# Sheet_2_2021-06-04.net
KiCad netlist of a schematic drawn in Altium Designer
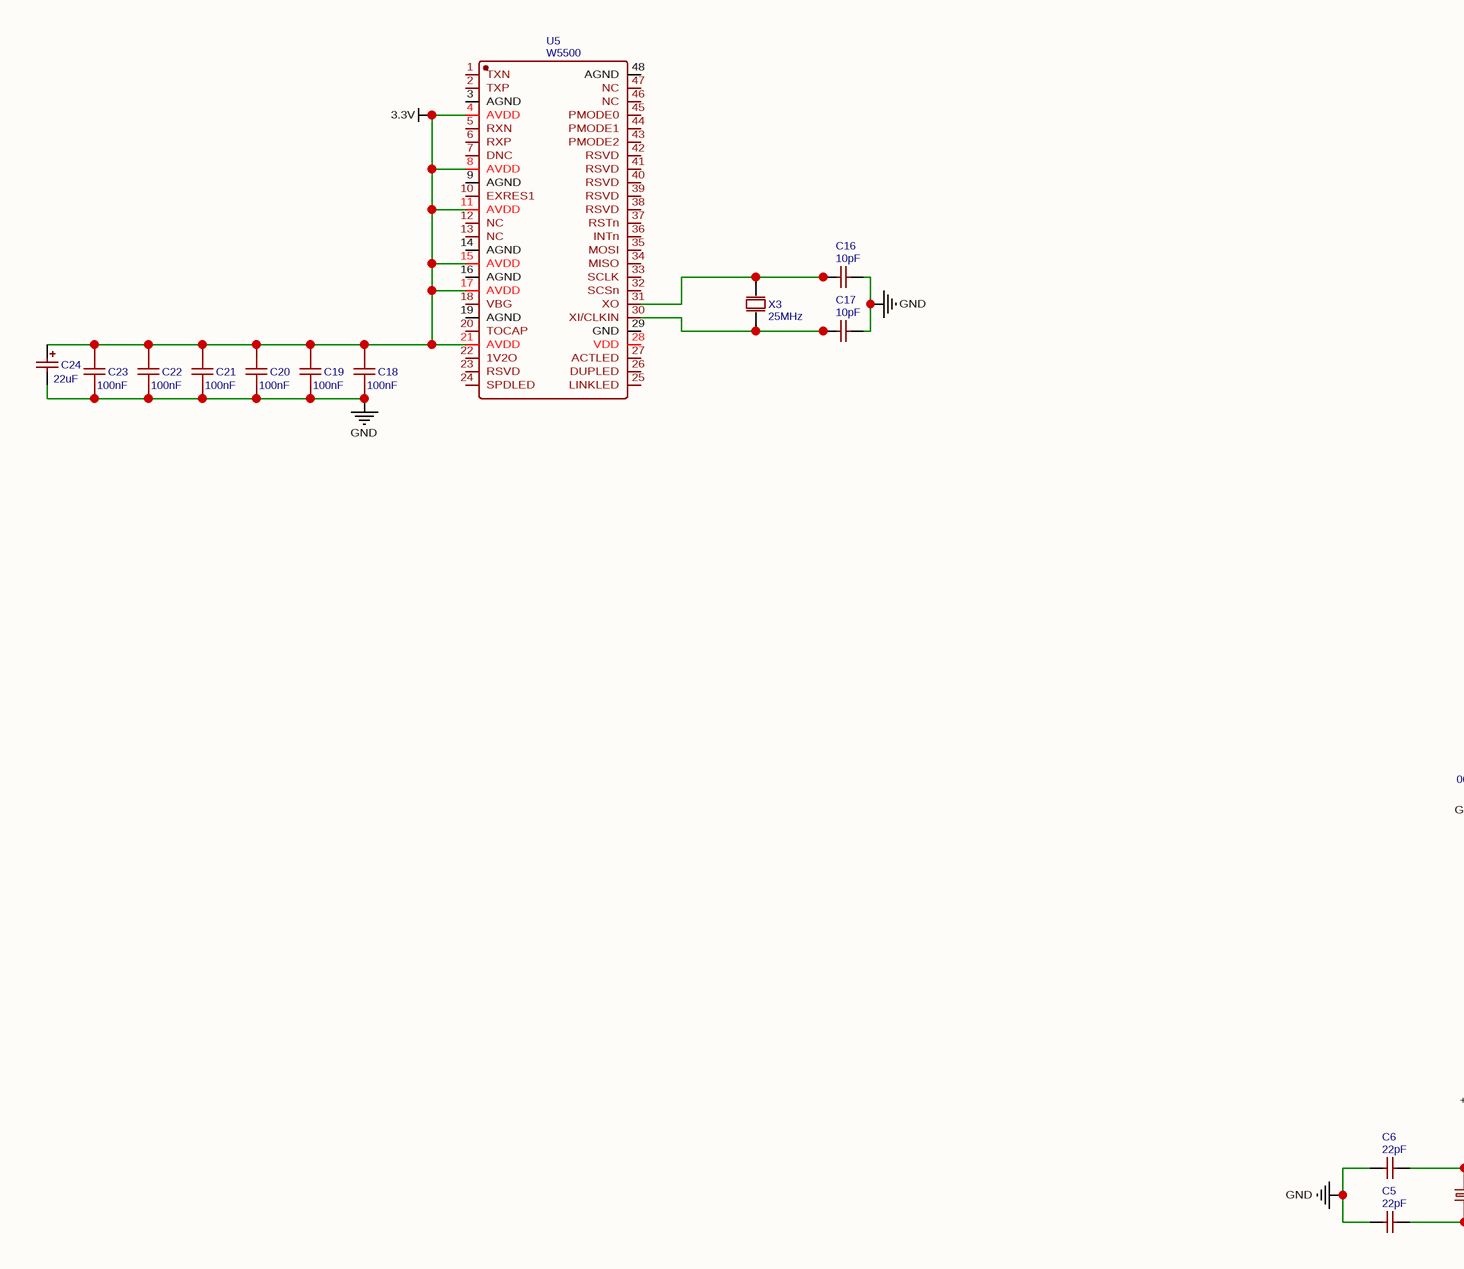
[diagram p0: Sheet_2_2021-06-04.schdoc, left]
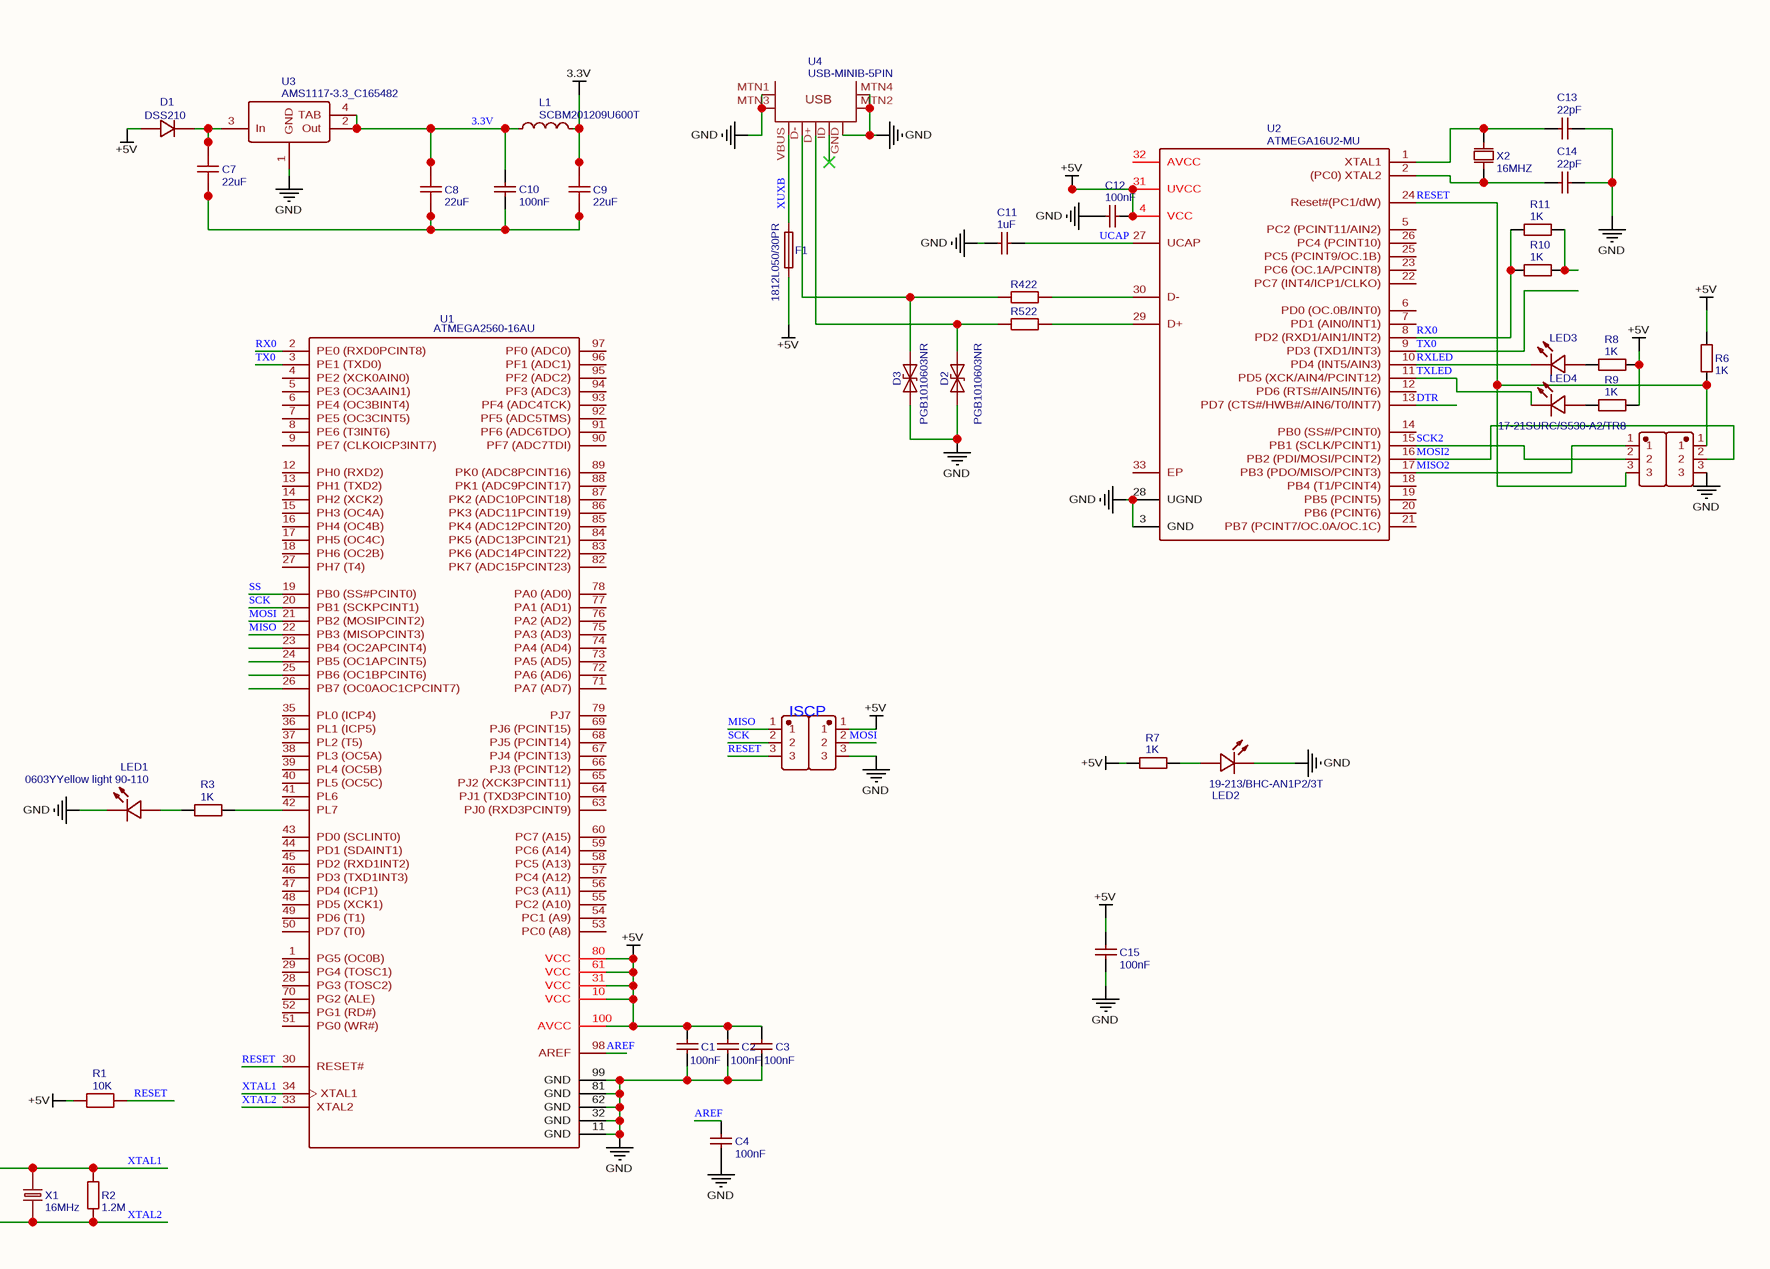
[diagram p1: Sheet_2_2021-06-04.schdoc, right]

(export (version "E")
  (design (tool "Eeschema 10.0.6"))
  (components
    (comp (ref "C1")
      (value "100nF")
      (fields
        (field (name "BOM_MANUFACTURER PART") "CL10B104JB8NNNC")
        (field (name "BOM_SUPPLIER PART") "C24452")
      )
      (libsource (lib "altium-import") (part "root_1_100nF_"))
    )
    (comp (ref "C2")
      (value "100nF")
      (fields
        (field (name "BOM_MANUFACTURER PART") "CL10B104JB8NNNC")
        (field (name "BOM_SUPPLIER PART") "C24452")
      )
      (libsource (lib "altium-import") (part "root_1_100nF_"))
    )
    (comp (ref "C3")
      (value "100nF")
      (fields
        (field (name "BOM_MANUFACTURER PART") "CL10B104JB8NNNC")
        (field (name "BOM_SUPPLIER PART") "C24452")
      )
      (libsource (lib "altium-import") (part "root_1_100nF_"))
    )
    (comp (ref "C4")
      (value "100nF")
      (fields
        (field (name "BOM_MANUFACTURER PART") "CL10B104JB8NNNC")
        (field (name "BOM_SUPPLIER PART") "C24452")
      )
      (libsource (lib "altium-import") (part "root_1_100nF_"))
    )
    (comp (ref "C5")
      (value "22pF")
      (fields
        (field (name "BOM_MANUFACTURER PART") "0201CG220J500NT")
        (field (name "BOM_SUPPLIER PART") "C57783")
      )
      (libsource (lib "altium-import") (part "root_0_22pF_"))
    )
    (comp (ref "C6")
      (value "22pF")
      (fields
        (field (name "BOM_MANUFACTURER PART") "0201CG220J500NT")
        (field (name "BOM_SUPPLIER PART") "C57783")
      )
      (libsource (lib "altium-import") (part "root_0_22pF_"))
    )
    (comp (ref "C7")
      (value "22uF")
      (fields
        (field (name "BOM_MANUFACTURER PART") "1206B226K160NT")
        (field (name "BOM_SUPPLIER PART") "C31847")
      )
      (libsource (lib "altium-import") (part "root_1_22uF_"))
    )
    (comp (ref "C8")
      (value "22uF")
      (fields
        (field (name "BOM_MANUFACTURER PART") "1206B226K160NT")
        (field (name "BOM_SUPPLIER PART") "C31847")
      )
      (libsource (lib "altium-import") (part "root_1_22uF_"))
    )
    (comp (ref "C9")
      (value "22uF")
      (fields
        (field (name "BOM_MANUFACTURER PART") "1206B226K160NT")
        (field (name "BOM_SUPPLIER PART") "C31847")
      )
      (libsource (lib "altium-import") (part "root_1_22uF_"))
    )
    (comp (ref "C10")
      (value "100nF")
      (fields
        (field (name "BOM_MANUFACTURER PART") "0402B104K160NT")
        (field (name "BOM_SUPPLIER PART") "C41851")
      )
      (libsource (lib "altium-import") (part "root_1_100nF_"))
    )
    (comp (ref "C11")
      (value "1uF")
      (fields
        (field (name "BOM_MANUFACTURER PART") "CL10A105KB8NNNC")
        (field (name "BOM_SUPPLIER PART") "C15849")
      )
      (libsource (lib "altium-import") (part "root_0_1uF_"))
    )
    (comp (ref "C12")
      (value "100nF")
      (fields
        (field (name "BOM_MANUFACTURER PART") "CL21F104ZBCNNNC")
        (field (name "BOM_SUPPLIER PART") "C1760")
      )
      (libsource (lib "altium-import") (part "root_0_100nF_"))
    )
    (comp (ref "C13")
      (value "22pF")
      (fields
        (field (name "BOM_MANUFACTURER PART") "0201CG220J500NT")
        (field (name "BOM_SUPPLIER PART") "C57783")
      )
      (libsource (lib "altium-import") (part "root_0_22pF_"))
    )
    (comp (ref "C14")
      (value "22pF")
      (fields
        (field (name "BOM_MANUFACTURER PART") "0201CG220J500NT")
        (field (name "BOM_SUPPLIER PART") "C57783")
      )
      (libsource (lib "altium-import") (part "root_0_22pF_"))
    )
    (comp (ref "C15")
      (value "100nF")
      (fields
        (field (name "BOM_MANUFACTURER PART") "0805B104K500NT")
        (field (name "BOM_SUPPLIER PART") "C38141")
      )
      (libsource (lib "altium-import") (part "root_1_100nF_"))
    )
    (comp (ref "C16")
      (value "10pF")
      (fields
        (field (name "BOM_MANUFACTURER PART") "0603CG100J201NT")
        (field (name "BOM_SUPPLIER PART") "C63673")
      )
      (libsource (lib "altium-import") (part "root_0_10pF_"))
    )
    (comp (ref "C17")
      (value "10pF")
      (fields
        (field (name "BOM_MANUFACTURER PART") "0603CG100J201NT")
        (field (name "BOM_SUPPLIER PART") "C63673")
      )
      (libsource (lib "altium-import") (part "root_0_10pF_"))
    )
    (comp (ref "C18")
      (value "100nF")
      (fields
        (field (name "BOM_MANUFACTURER PART") "GRM319R71H104KA01D")
        (field (name "BOM_SUPPLIER PART") "C86047")
      )
      (libsource (lib "") (part "root_1_100nF__1"))
    )
    (comp (ref "C19")
      (value "100nF")
      (fields
        (field (name "BOM_MANUFACTURER PART") "GRM319R71H104KA01D")
        (field (name "BOM_SUPPLIER PART") "C86047")
      )
      (libsource (lib "") (part "root_1_100nF__1"))
    )
    (comp (ref "C20")
      (value "100nF")
      (fields
        (field (name "BOM_MANUFACTURER PART") "GRM319R71H104KA01D")
        (field (name "BOM_SUPPLIER PART") "C86047")
      )
      (libsource (lib "") (part "root_1_100nF__1"))
    )
    (comp (ref "C21")
      (value "100nF")
      (fields
        (field (name "BOM_MANUFACTURER PART") "GRM319R71H104KA01D")
        (field (name "BOM_SUPPLIER PART") "C86047")
      )
      (libsource (lib "") (part "root_1_100nF__1"))
    )
    (comp (ref "C22")
      (value "100nF")
      (fields
        (field (name "BOM_MANUFACTURER PART") "GRM319R71H104KA01D")
        (field (name "BOM_SUPPLIER PART") "C86047")
      )
      (libsource (lib "") (part "root_1_100nF__1"))
    )
    (comp (ref "C23")
      (value "100nF")
      (fields
        (field (name "BOM_MANUFACTURER PART") "GRM319R71H104KA01D")
        (field (name "BOM_SUPPLIER PART") "C86047")
      )
      (libsource (lib "") (part "root_1_100nF__1"))
    )
    (comp (ref "C24")
      (value "22uF")
      (fields
        (field (name "BOM_MANUFACTURER PART") "CA45A-A-10V-22UF-K")
        (field (name "BOM_SUPPLIER PART") "C141745")
      )
      (libsource (lib "") (part "root_1_22uF__1"))
    )
    (comp (ref "D1")
      (value "DSS210")
      (fields (field (name "BOM_SUPPLIER PART") "C511868") (field (name "CONTRIBUTOR") "LCSC"))
      (libsource (lib "altium-import") (part "root_0_DSS210_"))
    )
    (comp (ref "D2")
      (value "PGB1010603NR")
      (fields (field (name "BOM_SUPPLIER PART") "C10677"))
      (libsource (lib "altium-import") (part "root_1_PGB1010603NR_"))
    )
    (comp (ref "D3")
      (value "PGB1010603NR")
      (fields (field (name "BOM_SUPPLIER PART") "C10677"))
      (libsource (lib "altium-import") (part "root_1_PGB1010603NR_"))
    )
    (comp (ref "F1")
      (value "1812L050/30PR")
      (fields (field (name "BOM_SUPPLIER PART") "C151168") (field (name "CONTRIBUTOR") "LCSC"))
      (libsource (lib "altium-import") (part "root_1_1812L050/30PR_"))
    )
    (comp (ref "H1")
      (value "Z-211-0311-0021-001")
      (fields (field (name "BOM_SUPPLIER PART") "C152153") (field (name "CONTRIBUTOR") "LCSC"))
      (libsource (lib "altium-import") (part "root_0_Z-211-0311-0021-001_"))
    )
    (comp (ref "H2")
      (value "Z-211-0311-0021-001")
      (fields (field (name "BOM_SUPPLIER PART") "C152153") (field (name "CONTRIBUTOR") "LCSC"))
      (libsource (lib "altium-import") (part "root_2_Z-211-0311-0021-001_"))
    )
    (comp (ref "H3")
      (value "Z-211-0311-0021-001")
      (fields (field (name "BOM_SUPPLIER PART") "C152153") (field (name "CONTRIBUTOR") "LCSC"))
      (libsource (lib "altium-import") (part "root_0_Z-211-0311-0021-001_"))
    )
    (comp (ref "H4")
      (value "Z-211-0311-0021-001")
      (fields (field (name "BOM_SUPPLIER PART") "C152153") (field (name "CONTRIBUTOR") "LCSC"))
      (libsource (lib "altium-import") (part "root_2_Z-211-0311-0021-001_"))
    )
    (comp (ref "L1")
      (value "SCBM201209U600T")
      (fields (field (name "BOM_SUPPLIER PART") "C494710") (field (name "CONTRIBUTOR") "LCSC"))
      (libsource (lib "altium-import") (part "root_0_SCBM201209U600T_"))
    )
    (comp (ref "LED1")
      (value "0603YYellow light 90-110")
      (fields
        (field (name "BOM_MANUFACTURER PART") "0603YYellow light 亮度90-110")
        (field (name "BOM_SUPPLIER PART") "C2287")
      )
      (libsource (lib "altium-import") (part "root_0_0603YYellow light 90-110_"))
    )
    (comp (ref "LED2")
      (value "19-213/BHC-AN1P2/3T")
      (fields (field (name "BOM_SUPPLIER PART") "C142304") (field (name "CONTRIBUTOR") "LCSC"))
      (libsource (lib "altium-import") (part "root_2_19-213/BHC-AN1P2/3T_"))
    )
    (comp (ref "LED3")
      (value "17-21SURC/S530-A2/TR8")
      (fields (field (name "BOM_SUPPLIER PART") "C131244") (field (name "CONTRIBUTOR") "LCSC"))
      (libsource (lib "altium-import") (part "root_0_17-21SURC/S530-A2/TR8_"))
    )
    (comp (ref "LED4")
      (value "17-21SURC/S530-A2/TR8")
      (fields (field (name "BOM_SUPPLIER PART") "C131244") (field (name "CONTRIBUTOR") "LCSC"))
      (libsource (lib "altium-import") (part "root_0_17-21SURC/S530-A2/TR8_"))
    )
    (comp (ref "R1")
      (value "10K")
      (fields
        (field (name "BOM_SUPPLIER PART") "C226679")
        (field (name "BOM_MANUFACTURER PART") "AC0402DR-0710KL")
        (field (name "CONTRIBUTOR") "LCSC")
      )
      (libsource (lib "altium-import") (part "root_0_10K_"))
    )
    (comp (ref "R2")
      (value "1.2M")
      (fields
        (field (name "BOM_SUPPLIER PART") "C150391")
        (field (name "BOM_MANUFACTURER PART") "HCR32-125FV")
        (field (name "CONTRIBUTOR") "LCSC")
      )
      (libsource (lib "altium-import") (part "root_1_1.2M_"))
    )
    (comp (ref "R3")
      (value "1K")
      (fields
        (field (name "BOM_MANUFACTURER PART") "1206W4F1001T5E")
        (field (name "BOM_SUPPLIER PART") "C4410")
      )
      (libsource (lib "altium-import") (part "root_0_1K_"))
    )
    (comp (ref "R4")
      (value "22")
      (fields
        (field (name "BOM_SUPPLIER PART") "C144722")
        (field (name "BOM_MANUFACTURER PART") "AC0402JR-0722RL")
        (field (name "CONTRIBUTOR") "LCSC")
      )
      (libsource (lib "altium-import") (part "root_0_22_"))
    )
    (comp (ref "R5")
      (value "22")
      (fields
        (field (name "BOM_SUPPLIER PART") "C144722")
        (field (name "BOM_MANUFACTURER PART") "AC0402JR-0722RL")
        (field (name "CONTRIBUTOR") "LCSC")
      )
      (libsource (lib "altium-import") (part "root_0_22_"))
    )
    (comp (ref "R6")
      (value "1K")
      (fields
        (field (name "BOM_MANUFACTURER PART") "1206W4F1001T5E")
        (field (name "BOM_SUPPLIER PART") "C4410")
      )
      (libsource (lib "altium-import") (part "root_1_1K_"))
    )
    (comp (ref "R7")
      (value "1K")
      (fields
        (field (name "BOM_MANUFACTURER PART") "1206W4J0102T5E")
        (field (name "BOM_SUPPLIER PART") "C1469")
      )
      (libsource (lib "altium-import") (part "root_0_1K_"))
    )
    (comp (ref "R8")
      (value "1K")
      (fields
        (field (name "BOM_MANUFACTURER PART") "1206W4J0102T5E")
        (field (name "BOM_SUPPLIER PART") "C1469")
      )
      (libsource (lib "altium-import") (part "root_0_1K_"))
    )
    (comp (ref "R9")
      (value "1K")
      (fields
        (field (name "BOM_MANUFACTURER PART") "1206W4J0102T5E")
        (field (name "BOM_SUPPLIER PART") "C1469")
      )
      (libsource (lib "altium-import") (part "root_0_1K_"))
    )
    (comp (ref "R10")
      (value "1K")
      (fields
        (field (name "BOM_MANUFACTURER PART") "RS-05K102JT")
        (field (name "BOM_SUPPLIER PART") "C115302")
      )
      (libsource (lib "altium-import") (part "root_0_1K_"))
    )
    (comp (ref "R11")
      (value "1K")
      (fields
        (field (name "BOM_MANUFACTURER PART") "RS-05K102JT")
        (field (name "BOM_SUPPLIER PART") "C115302")
      )
      (libsource (lib "altium-import") (part "root_0_1K_"))
    )
    (comp (ref "U1")
      (value "ATMEGA2560-16AU")
      (fields (field (name "BOM_SUPPLIER PART") "C22460"))
      (libsource (lib "altium-import") (part "root_0_ATMEGA2560-16AU_"))
    )
    (comp (ref "U2")
      (value "ATMEGA16U2-MU")
      (fields (field (name "BOM_SUPPLIER PART") "C17317"))
      (libsource (lib "altium-import") (part "root_0_ATMEGA16U2-MU_"))
    )
    (comp (ref "U3")
      (value "AMS1117-3.3_C165482")
      (fields
        (field (name "BOM_SUPPLIER PART") "C165482")
        (field (name "BOM_MANUFACTURER PART") "AMS1117-3.3")
        (field (name "CONTRIBUTOR") "LCSC")
      )
      (libsource (lib "altium-import") (part "root_0_AMS1117-3.3_C165482_"))
    )
    (comp (ref "U4")
      (value "USB-MINIB-5PIN")
      (description "Mini-USB B connector with 5th pin broken out.")
      (fields (field (name "CONTRIBUTOR") "SparkFun"))
      (libsource (lib "altium-import") (part "root_1_USB-MINIB-5PIN_"))
    )
    (comp (ref "U5")
      (value "W5500")
      (fields (field (name "BOM_SUPPLIER PART") "C32843"))
      (libsource (lib "altium-import") (part "root_0_W5500_"))
    )
    (comp (ref "X1")
      (value "16MHz")
      (fields
        (field (name "BOM_MANUFACTURER PART") "HC-49SM16MHz20pF30ppm")
        (field (name "BOM_SUPPLIER PART") "C111377")
      )
      (libsource (lib "altium-import") (part "root_1_16MHz_"))
    )
    (comp (ref "X2")
      (value "16MHZ")
      (fields
        (field (name "BOM_SUPPLIER PART") "C390745")
        (field (name "BOM_MANUFACTURER PART") "49SAC16000202060")
        (field (name "CONTRIBUTOR") "LCSC")
      )
      (libsource (lib "altium-import") (part "root_1_16MHZ_"))
    )
    (comp (ref "X3")
      (value "25MHz")
      (fields
        (field (name "BOM_MANUFACTURER PART") "X49SM25MSD2SC")
        (field (name "BOM_SUPPLIER PART") "C14872")
      )
      (libsource (lib "altium-import") (part "root_1_25MHz_"))
    )
  )
  (nets
    (net (code "1") (name "+5V") (class "Default")
      (node (ref "C1") (pin "2") (pinfunction "2_2") (pintype "passive"))
      (node (ref "C12") (pin "2") (pinfunction "2_2") (pintype "passive"))
      (node (ref "C15") (pin "2") (pinfunction "2_2") (pintype "passive"))
      (node (ref "C2") (pin "2") (pinfunction "2_2") (pintype "passive"))
      (node (ref "C3") (pin "2") (pinfunction "2_2") (pintype "passive"))
      (node (ref "D1") (pin "1") (pinfunction "A_1") (pintype "passive"))
      (node (ref "F1") (pin "1") (pinfunction "1_1") (pintype "passive"))
      (node (ref "H2") (pin "1") (pinfunction "1_1") (pintype "passive"))
      (node (ref "R1") (pin "1") (pinfunction "1_1") (pintype "passive"))
      (node (ref "R6") (pin "2") (pinfunction "2_2") (pintype "passive"))
      (node (ref "R7") (pin "1") (pinfunction "1_1") (pintype "passive"))
      (node (ref "R8") (pin "2") (pinfunction "2_2") (pintype "passive"))
      (node (ref "R9") (pin "2") (pinfunction "2_2") (pintype "passive"))
      (node (ref "U1") (pin "10") (pinfunction "VCC_10") (pintype "passive"))
      (node (ref "U1") (pin "100") (pinfunction "AVCC_100") (pintype "passive"))
      (node (ref "U1") (pin "31") (pinfunction "VCC_31") (pintype "passive"))
      (node (ref "U1") (pin "61") (pinfunction "VCC_61") (pintype "passive"))
      (node (ref "U1") (pin "80") (pinfunction "VCC_80") (pintype "passive"))
      (node (ref "U2") (pin "31") (pinfunction "UVCC_31") (pintype "passive"))
      (node (ref "U2") (pin "4") (pinfunction "VCC_4") (pintype "passive"))
    )
    (net (code "2") (name "/AREF") (class "Default")
      (node (ref "C4") (pin "2") (pinfunction "2_2") (pintype "passive"))
      (node (ref "U1") (pin "98") (pinfunction "AREF_98") (pintype "passive"))
    )
    (net (code "3") (name "/DTR") (class "Default")
      (node (ref "U2") (pin "13") (pinfunction "PD7_(CTS#/HWB#/AIN6/T0/INT7)_13") (pintype "passive"))
    )
    (net (code "4") (name "/MISO") (class "Default")
      (node (ref "H1") (pin "1") (pinfunction "1_1") (pintype "passive"))
      (node (ref "U1") (pin "22") (pinfunction "PB3_(MISOPCINT3)_22") (pintype "passive"))
    )
    (net (code "5") (name "/MISO2") (class "Default")
      (node (ref "H3") (pin "1") (pinfunction "1_1") (pintype "passive"))
      (node (ref "U2") (pin "17") (pinfunction "PB3_(PDO/MISO/PCINT3)_17") (pintype "passive"))
    )
    (net (code "6") (name "/MOSI") (class "Default")
      (node (ref "H2") (pin "2") (pinfunction "2_2") (pintype "passive"))
      (node (ref "U1") (pin "21") (pinfunction "PB2_(MOSIPCINT2)_21") (pintype "passive"))
    )
    (net (code "7") (name "/MOSI2") (class "Default")
      (node (ref "H4") (pin "2") (pinfunction "2_2") (pintype "passive"))
      (node (ref "U2") (pin "16") (pinfunction "PB2_(PDI/MOSI/PCINT2)_16") (pintype "passive"))
    )
    (net (code "8") (name "/RESET") (class "Default")
      (node (ref "H1") (pin "3") (pinfunction "3_3") (pintype "passive"))
      (node (ref "H3") (pin "3") (pinfunction "3_3") (pintype "passive"))
      (node (ref "H4") (pin "1") (pinfunction "1_1") (pintype "passive"))
      (node (ref "R1") (pin "2") (pinfunction "2_2") (pintype "passive"))
      (node (ref "R6") (pin "1") (pinfunction "1_1") (pintype "passive"))
      (node (ref "U1") (pin "30") (pinfunction "RESET#_30") (pintype "passive"))
      (node (ref "U2") (pin "24") (pinfunction "Reset#(PC1/dW)_24") (pintype "passive"))
    )
    (net (code "9") (name "/RX0") (class "Default")
      (node (ref "R10") (pin "1") (pinfunction "1_1") (pintype "passive"))
      (node (ref "R11") (pin "1") (pinfunction "1_1") (pintype "passive"))
      (node (ref "U1") (pin "2") (pinfunction "PE0_(RXD0PCINT8)_2") (pintype "passive"))
      (node (ref "U2") (pin "8") (pinfunction "PD2_(RXD1/AIN1/INT2)_8") (pintype "passive"))
    )
    (net (code "10") (name "/RXLED") (class "Default")
      (node (ref "LED3") (pin "1") (pinfunction "K_1") (pintype "passive"))
      (node (ref "U2") (pin "10") (pinfunction "PD4_(INT5/AIN3)_10") (pintype "passive"))
    )
    (net (code "11") (name "/SCK") (class "Default")
      (node (ref "H1") (pin "2") (pinfunction "2_2") (pintype "passive"))
      (node (ref "U1") (pin "20") (pinfunction "PB1_(SCKPCINT1)_20") (pintype "passive"))
    )
    (net (code "12") (name "/SCK2") (class "Default")
      (node (ref "H3") (pin "2") (pinfunction "2_2") (pintype "passive"))
      (node (ref "U2") (pin "15") (pinfunction "PB1_(SCLK/PCINT1)_15") (pintype "passive"))
    )
    (net (code "13") (name "/SS") (class "Default")
      (node (ref "U1") (pin "19") (pinfunction "PB0_(SS#PCINT0)_19") (pintype "passive"))
    )
    (net (code "14") (name "/TX0") (class "Default")
      (node (ref "U1") (pin "3") (pinfunction "PE1_(TXD0)_3") (pintype "passive"))
      (node (ref "U2") (pin "9") (pinfunction "PD3_(TXD1/INT3)_9") (pintype "passive"))
    )
    (net (code "15") (name "/TXLED") (class "Default")
      (node (ref "LED4") (pin "1") (pinfunction "K_1") (pintype "passive"))
      (node (ref "U2") (pin "11") (pinfunction "PD5_(XCK/AIN4/PCINT12)_11") (pintype "passive"))
    )
    (net (code "16") (name "/UCAP") (class "Default")
      (node (ref "C11") (pin "2") (pinfunction "2_2") (pintype "passive"))
      (node (ref "U2") (pin "27") (pinfunction "UCAP_27") (pintype "passive"))
    )
    (net (code "17") (name "/XTAL1") (class "Default")
      (node (ref "C6") (pin "2") (pinfunction "2_2") (pintype "passive"))
      (node (ref "R2") (pin "2") (pinfunction "2_2") (pintype "passive"))
      (node (ref "U1") (pin "34") (pinfunction "XTAL1_34") (pintype "passive"))
      (node (ref "X1") (pin "2") (pinfunction "2_2") (pintype "passive"))
    )
    (net (code "18") (name "/XTAL2") (class "Default")
      (node (ref "C5") (pin "2") (pinfunction "2_2") (pintype "passive"))
      (node (ref "R2") (pin "1") (pinfunction "1_1") (pintype "passive"))
      (node (ref "U1") (pin "33") (pinfunction "XTAL2_33") (pintype "passive"))
      (node (ref "X1") (pin "1") (pinfunction "1_1") (pintype "passive"))
    )
    (net (code "19") (name "/XUXB") (class "Default")
      (node (ref "F1") (pin "2") (pinfunction "2_2") (pintype "passive"))
      (node (ref "U4") (pin "VBUS") (pinfunction "VBUS_VBUS") (pintype "passive"))
    )
    (net (code "20") (name "3.3V") (class "Default")
      (node (ref "C10") (pin "2") (pinfunction "2_2") (pintype "passive"))
      (node (ref "C18") (pin "2") (pinfunction "2_2") (pintype "passive"))
      (node (ref "C19") (pin "2") (pinfunction "2_2") (pintype "passive"))
      (node (ref "C20") (pin "2") (pinfunction "2_2") (pintype "passive"))
      (node (ref "C21") (pin "2") (pinfunction "2_2") (pintype "passive"))
      (node (ref "C22") (pin "2") (pinfunction "2_2") (pintype "passive"))
      (node (ref "C23") (pin "2") (pinfunction "2_2") (pintype "passive"))
      (node (ref "C24") (pin "1") (pinfunction "1_1") (pintype "passive"))
      (node (ref "C8") (pin "2") (pinfunction "2_2") (pintype "passive"))
      (node (ref "C9") (pin "2") (pinfunction "2_2") (pintype "passive"))
      (node (ref "L1") (pin "1") (pinfunction "1_1") (pintype "passive"))
      (node (ref "L1") (pin "2") (pinfunction "2_2") (pintype "passive"))
      (node (ref "U3") (pin "2") (pinfunction "Out_2") (pintype "passive"))
      (node (ref "U3") (pin "4") (pinfunction "TAB_4") (pintype "passive"))
      (node (ref "U5") (pin "11") (pinfunction "AVDD_11") (pintype "passive"))
      (node (ref "U5") (pin "15") (pinfunction "AVDD_15") (pintype "passive"))
      (node (ref "U5") (pin "17") (pinfunction "AVDD_17") (pintype "passive"))
      (node (ref "U5") (pin "21") (pinfunction "AVDD_21") (pintype "passive"))
      (node (ref "U5") (pin "4") (pinfunction "AVDD_4") (pintype "passive"))
      (node (ref "U5") (pin "8") (pinfunction "AVDD_8") (pintype "passive"))
    )
    (net (code "21") (name "GND") (class "Default")
      (node (ref "C1") (pin "1") (pinfunction "1_1") (pintype "passive"))
      (node (ref "C11") (pin "1") (pinfunction "1_1") (pintype "passive"))
      (node (ref "C12") (pin "1") (pinfunction "1_1") (pintype "passive"))
      (node (ref "C13") (pin "2") (pinfunction "2_2") (pintype "passive"))
      (node (ref "C14") (pin "2") (pinfunction "2_2") (pintype "passive"))
      (node (ref "C15") (pin "1") (pinfunction "1_1") (pintype "passive"))
      (node (ref "C16") (pin "2") (pinfunction "2_2") (pintype "passive"))
      (node (ref "C17") (pin "2") (pinfunction "2_2") (pintype "passive"))
      (node (ref "C18") (pin "1") (pinfunction "1_1") (pintype "passive"))
      (node (ref "C19") (pin "1") (pinfunction "1_1") (pintype "passive"))
      (node (ref "C2") (pin "1") (pinfunction "1_1") (pintype "passive"))
      (node (ref "C20") (pin "1") (pinfunction "1_1") (pintype "passive"))
      (node (ref "C21") (pin "1") (pinfunction "1_1") (pintype "passive"))
      (node (ref "C22") (pin "1") (pinfunction "1_1") (pintype "passive"))
      (node (ref "C23") (pin "1") (pinfunction "1_1") (pintype "passive"))
      (node (ref "C24") (pin "2") (pinfunction "2_2") (pintype "passive"))
      (node (ref "C3") (pin "1") (pinfunction "1_1") (pintype "passive"))
      (node (ref "C4") (pin "1") (pinfunction "1_1") (pintype "passive"))
      (node (ref "C5") (pin "1") (pinfunction "1_1") (pintype "passive"))
      (node (ref "C6") (pin "1") (pinfunction "1_1") (pintype "passive"))
      (node (ref "D2") (pin "1") (pinfunction "1_1") (pintype "passive"))
      (node (ref "D3") (pin "1") (pinfunction "1_1") (pintype "passive"))
      (node (ref "H2") (pin "3") (pinfunction "3_3") (pintype "passive"))
      (node (ref "H4") (pin "3") (pinfunction "3_3") (pintype "passive"))
      (node (ref "LED1") (pin "2") (pinfunction "K_2") (pintype "passive"))
      (node (ref "LED2") (pin "1") (pinfunction "K_1") (pintype "passive"))
      (node (ref "U1") (pin "11") (pinfunction "GND_11") (pintype "passive"))
      (node (ref "U1") (pin "32") (pinfunction "GND_32") (pintype "passive"))
      (node (ref "U1") (pin "62") (pinfunction "GND_62") (pintype "passive"))
      (node (ref "U1") (pin "81") (pinfunction "GND_81") (pintype "passive"))
      (node (ref "U1") (pin "99") (pinfunction "GND_99") (pintype "passive"))
      (node (ref "U2") (pin "28") (pinfunction "UGND_28") (pintype "passive"))
      (node (ref "U2") (pin "3") (pinfunction "GND_3") (pintype "passive"))
      (node (ref "U3") (pin "1") (pinfunction "GND_1") (pintype "passive"))
      (node (ref "U4") (pin "GND") (pinfunction "GND_GND") (pintype "passive"))
      (node (ref "U4") (pin "MTN1") (pinfunction "MTN2_MTN1") (pintype "passive"))
      (node (ref "U4") (pin "MTN2") (pinfunction "MTN3_MTN2") (pintype "passive"))
      (node (ref "U4") (pin "MTN3") (pinfunction "MTN1_MTN3") (pintype "passive"))
      (node (ref "U4") (pin "MTN4") (pinfunction "MTN4_MTN4") (pintype "passive"))
    )
    (net (code "22") (name "Net-(C10-Pad1)") (class "Default")
      (node (ref "C10") (pin "1") (pinfunction "1_1") (pintype "passive"))
      (node (ref "C7") (pin "1") (pinfunction "1_1") (pintype "passive"))
      (node (ref "C8") (pin "1") (pinfunction "1_1") (pintype "passive"))
      (node (ref "C9") (pin "1") (pinfunction "1_1") (pintype "passive"))
    )
    (net (code "23") (name "Net-(D1-K)") (class "Default")
      (node (ref "C7") (pin "2") (pinfunction "2_2") (pintype "passive"))
      (node (ref "D1") (pin "2") (pinfunction "K_2") (pintype "passive"))
      (node (ref "U3") (pin "3") (pinfunction "In_3") (pintype "passive"))
    )
    (net (code "24") (name "Net-(D2-Pad2)") (class "Default")
      (node (ref "D2") (pin "2") (pinfunction "2_2") (pintype "passive"))
      (node (ref "R5") (pin "1") (pinfunction "1_1") (pintype "passive"))
      (node (ref "U4") (pin "D+") (pinfunction "D+_D+") (pintype "passive"))
    )
    (net (code "25") (name "Net-(D3-Pad2)") (class "Default")
      (node (ref "D3") (pin "2") (pinfunction "2_2") (pintype "passive"))
      (node (ref "R4") (pin "1") (pinfunction "1_1") (pintype "passive"))
      (node (ref "U4") (pin "D-") (pinfunction "D-_D-") (pintype "passive"))
    )
    (net (code "26") (name "Net-(LED1-A)") (class "Default")
      (node (ref "LED1") (pin "1") (pinfunction "A_1") (pintype "passive"))
      (node (ref "R3") (pin "1") (pinfunction "1_1") (pintype "passive"))
    )
    (net (code "27") (name "Net-(LED2-A)") (class "Default")
      (node (ref "LED2") (pin "2") (pinfunction "A_2") (pintype "passive"))
      (node (ref "R7") (pin "2") (pinfunction "2_2") (pintype "passive"))
    )
    (net (code "28") (name "Net-(LED3-A)") (class "Default")
      (node (ref "LED3") (pin "2") (pinfunction "A_2") (pintype "passive"))
      (node (ref "R8") (pin "1") (pinfunction "1_1") (pintype "passive"))
    )
    (net (code "29") (name "Net-(LED4-A)") (class "Default")
      (node (ref "LED4") (pin "2") (pinfunction "A_2") (pintype "passive"))
      (node (ref "R9") (pin "1") (pinfunction "1_1") (pintype "passive"))
    )
    (net (code "30") (name "Net-(R10-Pad2)") (class "Default")
      (node (ref "R10") (pin "2") (pinfunction "2_2") (pintype "passive"))
      (node (ref "R11") (pin "2") (pinfunction "2_2") (pintype "passive"))
    )
    (net (code "31") (name "Net-(U1-PL7)") (class "Default")
      (node (ref "R3") (pin "2") (pinfunction "2_2") (pintype "passive"))
      (node (ref "U1") (pin "42") (pinfunction "PL7_42") (pintype "passive"))
    )
    (net (code "32") (name "Net-(U2-(PC0)_XTAL2)") (class "Default")
      (node (ref "C14") (pin "1") (pinfunction "1_1") (pintype "passive"))
      (node (ref "U2") (pin "2") (pinfunction "(PC0)_XTAL2_2") (pintype "passive"))
      (node (ref "X2") (pin "1") (pinfunction "OSC1_1") (pintype "passive"))
    )
    (net (code "33") (name "Net-(U2-D+)") (class "Default")
      (node (ref "R5") (pin "2") (pinfunction "2_2") (pintype "passive"))
      (node (ref "U2") (pin "29") (pinfunction "D+_29") (pintype "passive"))
    )
    (net (code "34") (name "Net-(U2-D-)") (class "Default")
      (node (ref "R4") (pin "2") (pinfunction "2_2") (pintype "passive"))
      (node (ref "U2") (pin "30") (pinfunction "D-_30") (pintype "passive"))
    )
    (net (code "35") (name "Net-(U2-XTAL1)") (class "Default")
      (node (ref "C13") (pin "1") (pinfunction "1_1") (pintype "passive"))
      (node (ref "U2") (pin "1") (pinfunction "XTAL1_1") (pintype "passive"))
      (node (ref "X2") (pin "2") (pinfunction "OSC2_2") (pintype "passive"))
    )
    (net (code "36") (name "Net-(U5-XI{slash}CLKIN)") (class "Default")
      (node (ref "C17") (pin "1") (pinfunction "1_1") (pintype "passive"))
      (node (ref "U5") (pin "30") (pinfunction "XI/CLKIN_30") (pintype "passive"))
      (node (ref "X3") (pin "1") (pinfunction "OSC1_1") (pintype "passive"))
    )
    (net (code "37") (name "Net-(U5-XO)") (class "Default")
      (node (ref "C16") (pin "1") (pinfunction "1_1") (pintype "passive"))
      (node (ref "U5") (pin "31") (pinfunction "XO_31") (pintype "passive"))
      (node (ref "X3") (pin "2") (pinfunction "OSC2_2") (pintype "passive"))
    )
    (net (code "38") (name "unconnected-(U1-PA0_(AD0)-Pad78)") (class "Default")
      (node (ref "U1") (pin "78") (pinfunction "PA0_(AD0)_78") (pintype "passive"))
    )
    (net (code "39") (name "unconnected-(U1-PA1_(AD1)-Pad77)") (class "Default")
      (node (ref "U1") (pin "77") (pinfunction "PA1_(AD1)_77") (pintype "passive"))
    )
    (net (code "40") (name "unconnected-(U1-PA2_(AD2)-Pad76)") (class "Default")
      (node (ref "U1") (pin "76") (pinfunction "PA2_(AD2)_76") (pintype "passive"))
    )
    (net (code "41") (name "unconnected-(U1-PA3_(AD3)-Pad75)") (class "Default")
      (node (ref "U1") (pin "75") (pinfunction "PA3_(AD3)_75") (pintype "passive"))
    )
    (net (code "42") (name "unconnected-(U1-PA4_(AD4)-Pad74)") (class "Default")
      (node (ref "U1") (pin "74") (pinfunction "PA4_(AD4)_74") (pintype "passive"))
    )
    (net (code "43") (name "unconnected-(U1-PA5_(AD5)-Pad73)") (class "Default")
      (node (ref "U1") (pin "73") (pinfunction "PA5_(AD5)_73") (pintype "passive"))
    )
    (net (code "44") (name "unconnected-(U1-PA6_(AD6)-Pad72)") (class "Default")
      (node (ref "U1") (pin "72") (pinfunction "PA6_(AD6)_72") (pintype "passive"))
    )
    (net (code "45") (name "unconnected-(U1-PA7_(AD7)-Pad71)") (class "Default")
      (node (ref "U1") (pin "71") (pinfunction "PA7_(AD7)_71") (pintype "passive"))
    )
    (net (code "46") (name "unconnected-(U1-PB4_(OC2APCINT4)-Pad23)") (class "Default")
      (node (ref "U1") (pin "23") (pinfunction "PB4_(OC2APCINT4)_23") (pintype "passive"))
    )
    (net (code "47") (name "unconnected-(U1-PB5_(OC1APCINT5)-Pad24)") (class "Default")
      (node (ref "U1") (pin "24") (pinfunction "PB5_(OC1APCINT5)_24") (pintype "passive"))
    )
    (net (code "48") (name "unconnected-(U1-PB6_(OC1BPCINT6)-Pad25)") (class "Default")
      (node (ref "U1") (pin "25") (pinfunction "PB6_(OC1BPCINT6)_25") (pintype "passive"))
    )
    (net (code "49") (name "unconnected-(U1-PB7_(OC0AOC1CPCINT7)-Pad26)") (class "Default")
      (node (ref "U1") (pin "26") (pinfunction "PB7_(OC0AOC1CPCINT7)_26") (pintype "passive"))
    )
    (net (code "50") (name "unconnected-(U1-PC0_(A8)-Pad53)") (class "Default")
      (node (ref "U1") (pin "53") (pinfunction "PC0_(A8)_53") (pintype "passive"))
    )
    (net (code "51") (name "unconnected-(U1-PC1_(A9)-Pad54)") (class "Default")
      (node (ref "U1") (pin "54") (pinfunction "PC1_(A9)_54") (pintype "passive"))
    )
    (net (code "52") (name "unconnected-(U1-PC2_(A10)-Pad55)") (class "Default")
      (node (ref "U1") (pin "55") (pinfunction "PC2_(A10)_55") (pintype "passive"))
    )
    (net (code "53") (name "unconnected-(U1-PC3_(A11)-Pad56)") (class "Default")
      (node (ref "U1") (pin "56") (pinfunction "PC3_(A11)_56") (pintype "passive"))
    )
    (net (code "54") (name "unconnected-(U1-PC4_(A12)-Pad57)") (class "Default")
      (node (ref "U1") (pin "57") (pinfunction "PC4_(A12)_57") (pintype "passive"))
    )
    (net (code "55") (name "unconnected-(U1-PC5_(A13)-Pad58)") (class "Default")
      (node (ref "U1") (pin "58") (pinfunction "PC5_(A13)_58") (pintype "passive"))
    )
    (net (code "56") (name "unconnected-(U1-PC6_(A14)-Pad59)") (class "Default")
      (node (ref "U1") (pin "59") (pinfunction "PC6_(A14)_59") (pintype "passive"))
    )
    (net (code "57") (name "unconnected-(U1-PC7_(A15)-Pad60)") (class "Default")
      (node (ref "U1") (pin "60") (pinfunction "PC7_(A15)_60") (pintype "passive"))
    )
    (net (code "58") (name "unconnected-(U1-PD0_(SCLINT0)-Pad43)") (class "Default")
      (node (ref "U1") (pin "43") (pinfunction "PD0_(SCLINT0)_43") (pintype "passive"))
    )
    (net (code "59") (name "unconnected-(U1-PD1_(SDAINT1)-Pad44)") (class "Default")
      (node (ref "U1") (pin "44") (pinfunction "PD1_(SDAINT1)_44") (pintype "passive"))
    )
    (net (code "60") (name "unconnected-(U1-PD2_(RXD1INT2)-Pad45)") (class "Default")
      (node (ref "U1") (pin "45") (pinfunction "PD2_(RXD1INT2)_45") (pintype "passive"))
    )
    (net (code "61") (name "unconnected-(U1-PD3_(TXD1INT3)-Pad46)") (class "Default")
      (node (ref "U1") (pin "46") (pinfunction "PD3_(TXD1INT3)_46") (pintype "passive"))
    )
    (net (code "62") (name "unconnected-(U1-PD4_(ICP1)-Pad47)") (class "Default")
      (node (ref "U1") (pin "47") (pinfunction "PD4_(ICP1)_47") (pintype "passive"))
    )
    (net (code "63") (name "unconnected-(U1-PD5_(XCK1)-Pad48)") (class "Default")
      (node (ref "U1") (pin "48") (pinfunction "PD5_(XCK1)_48") (pintype "passive"))
    )
    (net (code "64") (name "unconnected-(U1-PD6_(T1)-Pad49)") (class "Default")
      (node (ref "U1") (pin "49") (pinfunction "PD6_(T1)_49") (pintype "passive"))
    )
    (net (code "65") (name "unconnected-(U1-PD7_(T0)-Pad50)") (class "Default")
      (node (ref "U1") (pin "50") (pinfunction "PD7_(T0)_50") (pintype "passive"))
    )
    (net (code "66") (name "unconnected-(U1-PE2_(XCK0AIN0)-Pad4)") (class "Default")
      (node (ref "U1") (pin "4") (pinfunction "PE2_(XCK0AIN0)_4") (pintype "passive"))
    )
    (net (code "67") (name "unconnected-(U1-PE3_(OC3AAIN1)-Pad5)") (class "Default")
      (node (ref "U1") (pin "5") (pinfunction "PE3_(OC3AAIN1)_5") (pintype "passive"))
    )
    (net (code "68") (name "unconnected-(U1-PE4_(OC3BINT4)-Pad6)") (class "Default")
      (node (ref "U1") (pin "6") (pinfunction "PE4_(OC3BINT4)_6") (pintype "passive"))
    )
    (net (code "69") (name "unconnected-(U1-PE5_(OC3CINT5)-Pad7)") (class "Default")
      (node (ref "U1") (pin "7") (pinfunction "PE5_(OC3CINT5)_7") (pintype "passive"))
    )
    (net (code "70") (name "unconnected-(U1-PE6_(T3INT6)-Pad8)") (class "Default")
      (node (ref "U1") (pin "8") (pinfunction "PE6_(T3INT6)_8") (pintype "passive"))
    )
    (net (code "71") (name "unconnected-(U1-PE7_(CLKOICP3INT7)-Pad9)") (class "Default")
      (node (ref "U1") (pin "9") (pinfunction "PE7_(CLKOICP3INT7)_9") (pintype "passive"))
    )
    (net (code "72") (name "unconnected-(U1-PF0_(ADC0)-Pad97)") (class "Default")
      (node (ref "U1") (pin "97") (pinfunction "PF0_(ADC0)_97") (pintype "passive"))
    )
    (net (code "73") (name "unconnected-(U1-PF1_(ADC1)-Pad96)") (class "Default")
      (node (ref "U1") (pin "96") (pinfunction "PF1_(ADC1)_96") (pintype "passive"))
    )
    (net (code "74") (name "unconnected-(U1-PF2_(ADC2)-Pad95)") (class "Default")
      (node (ref "U1") (pin "95") (pinfunction "PF2_(ADC2)_95") (pintype "passive"))
    )
    (net (code "75") (name "unconnected-(U1-PF3_(ADC3)-Pad94)") (class "Default")
      (node (ref "U1") (pin "94") (pinfunction "PF3_(ADC3)_94") (pintype "passive"))
    )
    (net (code "76") (name "unconnected-(U1-PF4_(ADC4TCK)-Pad93)") (class "Default")
      (node (ref "U1") (pin "93") (pinfunction "PF4_(ADC4TCK)_93") (pintype "passive"))
    )
    (net (code "77") (name "unconnected-(U1-PF5_(ADC5TMS)-Pad92)") (class "Default")
      (node (ref "U1") (pin "92") (pinfunction "PF5_(ADC5TMS)_92") (pintype "passive"))
    )
    (net (code "78") (name "unconnected-(U1-PF6_(ADC6TDO)-Pad91)") (class "Default")
      (node (ref "U1") (pin "91") (pinfunction "PF6_(ADC6TDO)_91") (pintype "passive"))
    )
    (net (code "79") (name "unconnected-(U1-PF7_(ADC7TDI)-Pad90)") (class "Default")
      (node (ref "U1") (pin "90") (pinfunction "PF7_(ADC7TDI)_90") (pintype "passive"))
    )
    (net (code "80") (name "unconnected-(U1-PG0_(WR#)-Pad51)") (class "Default")
      (node (ref "U1") (pin "51") (pinfunction "PG0_(WR#)_51") (pintype "passive"))
    )
    (net (code "81") (name "unconnected-(U1-PG1_(RD#)-Pad52)") (class "Default")
      (node (ref "U1") (pin "52") (pinfunction "PG1_(RD#)_52") (pintype "passive"))
    )
    (net (code "82") (name "unconnected-(U1-PG2_(ALE)-Pad70)") (class "Default")
      (node (ref "U1") (pin "70") (pinfunction "PG2_(ALE)_70") (pintype "passive"))
    )
    (net (code "83") (name "unconnected-(U1-PG3_(TOSC2)-Pad28)") (class "Default")
      (node (ref "U1") (pin "28") (pinfunction "PG3_(TOSC2)_28") (pintype "passive"))
    )
    (net (code "84") (name "unconnected-(U1-PG4_(TOSC1)-Pad29)") (class "Default")
      (node (ref "U1") (pin "29") (pinfunction "PG4_(TOSC1)_29") (pintype "passive"))
    )
    (net (code "85") (name "unconnected-(U1-PG5_(OC0B)-Pad1)") (class "Default")
      (node (ref "U1") (pin "1") (pinfunction "PG5_(OC0B)_1") (pintype "passive"))
    )
    (net (code "86") (name "unconnected-(U1-PH0_(RXD2)-Pad12)") (class "Default")
      (node (ref "U1") (pin "12") (pinfunction "PH0_(RXD2)_12") (pintype "passive"))
    )
    (net (code "87") (name "unconnected-(U1-PH1_(TXD2)-Pad13)") (class "Default")
      (node (ref "U1") (pin "13") (pinfunction "PH1_(TXD2)_13") (pintype "passive"))
    )
    (net (code "88") (name "unconnected-(U1-PH2_(XCK2)-Pad14)") (class "Default")
      (node (ref "U1") (pin "14") (pinfunction "PH2_(XCK2)_14") (pintype "passive"))
    )
    (net (code "89") (name "unconnected-(U1-PH3_(OC4A)-Pad15)") (class "Default")
      (node (ref "U1") (pin "15") (pinfunction "PH3_(OC4A)_15") (pintype "passive"))
    )
    (net (code "90") (name "unconnected-(U1-PH4_(OC4B)-Pad16)") (class "Default")
      (node (ref "U1") (pin "16") (pinfunction "PH4_(OC4B)_16") (pintype "passive"))
    )
    (net (code "91") (name "unconnected-(U1-PH5_(OC4C)-Pad17)") (class "Default")
      (node (ref "U1") (pin "17") (pinfunction "PH5_(OC4C)_17") (pintype "passive"))
    )
    (net (code "92") (name "unconnected-(U1-PH6_(OC2B)-Pad18)") (class "Default")
      (node (ref "U1") (pin "18") (pinfunction "PH6_(OC2B)_18") (pintype "passive"))
    )
    (net (code "93") (name "unconnected-(U1-PH7_(T4)-Pad27)") (class "Default")
      (node (ref "U1") (pin "27") (pinfunction "PH7_(T4)_27") (pintype "passive"))
    )
    (net (code "94") (name "unconnected-(U1-PJ0_(RXD3PCINT9)-Pad63)") (class "Default")
      (node (ref "U1") (pin "63") (pinfunction "PJ0_(RXD3PCINT9)_63") (pintype "passive"))
    )
    (net (code "95") (name "unconnected-(U1-PJ1_(TXD3PCINT10)-Pad64)") (class "Default")
      (node (ref "U1") (pin "64") (pinfunction "PJ1_(TXD3PCINT10)_64") (pintype "passive"))
    )
    (net (code "96") (name "unconnected-(U1-PJ2_(XCK3PCINT11)-Pad65)") (class "Default")
      (node (ref "U1") (pin "65") (pinfunction "PJ2_(XCK3PCINT11)_65") (pintype "passive"))
    )
    (net (code "97") (name "unconnected-(U1-PJ3_(PCINT12)-Pad66)") (class "Default")
      (node (ref "U1") (pin "66") (pinfunction "PJ3_(PCINT12)_66") (pintype "passive"))
    )
    (net (code "98") (name "unconnected-(U1-PJ4_(PCINT13)-Pad67)") (class "Default")
      (node (ref "U1") (pin "67") (pinfunction "PJ4_(PCINT13)_67") (pintype "passive"))
    )
    (net (code "99") (name "unconnected-(U1-PJ5_(PCINT14)-Pad68)") (class "Default")
      (node (ref "U1") (pin "68") (pinfunction "PJ5_(PCINT14)_68") (pintype "passive"))
    )
    (net (code "100") (name "unconnected-(U1-PJ6_(PCINT15)-Pad69)") (class "Default")
      (node (ref "U1") (pin "69") (pinfunction "PJ6_(PCINT15)_69") (pintype "passive"))
    )
    (net (code "101") (name "unconnected-(U1-PJ7-Pad79)") (class "Default")
      (node (ref "U1") (pin "79") (pinfunction "PJ7_79") (pintype "passive"))
    )
    (net (code "102") (name "unconnected-(U1-PK0_(ADC8PCINT16)-Pad89)") (class "Default")
      (node (ref "U1") (pin "89") (pinfunction "PK0_(ADC8PCINT16)_89") (pintype "passive"))
    )
    (net (code "103") (name "unconnected-(U1-PK1_(ADC9PCINT17)-Pad88)") (class "Default")
      (node (ref "U1") (pin "88") (pinfunction "PK1_(ADC9PCINT17)_88") (pintype "passive"))
    )
    (net (code "104") (name "unconnected-(U1-PK2_(ADC10PCINT18)-Pad87)") (class "Default")
      (node (ref "U1") (pin "87") (pinfunction "PK2_(ADC10PCINT18)_87") (pintype "passive"))
    )
    (net (code "105") (name "unconnected-(U1-PK3_(ADC11PCINT19)-Pad86)") (class "Default")
      (node (ref "U1") (pin "86") (pinfunction "PK3_(ADC11PCINT19)_86") (pintype "passive"))
    )
    (net (code "106") (name "unconnected-(U1-PK4_(ADC12PCINT20)-Pad85)") (class "Default")
      (node (ref "U1") (pin "85") (pinfunction "PK4_(ADC12PCINT20)_85") (pintype "passive"))
    )
    (net (code "107") (name "unconnected-(U1-PK5_(ADC13PCINT21)-Pad84)") (class "Default")
      (node (ref "U1") (pin "84") (pinfunction "PK5_(ADC13PCINT21)_84") (pintype "passive"))
    )
    (net (code "108") (name "unconnected-(U1-PK6_(ADC14PCINT22)-Pad83)") (class "Default")
      (node (ref "U1") (pin "83") (pinfunction "PK6_(ADC14PCINT22)_83") (pintype "passive"))
    )
    (net (code "109") (name "unconnected-(U1-PK7_(ADC15PCINT23)-Pad82)") (class "Default")
      (node (ref "U1") (pin "82") (pinfunction "PK7_(ADC15PCINT23)_82") (pintype "passive"))
    )
    (net (code "110") (name "unconnected-(U1-PL0_(ICP4)-Pad35)") (class "Default")
      (node (ref "U1") (pin "35") (pinfunction "PL0_(ICP4)_35") (pintype "passive"))
    )
    (net (code "111") (name "unconnected-(U1-PL1_(ICP5)-Pad36)") (class "Default")
      (node (ref "U1") (pin "36") (pinfunction "PL1_(ICP5)_36") (pintype "passive"))
    )
    (net (code "112") (name "unconnected-(U1-PL2_(T5)-Pad37)") (class "Default")
      (node (ref "U1") (pin "37") (pinfunction "PL2_(T5)_37") (pintype "passive"))
    )
    (net (code "113") (name "unconnected-(U1-PL3_(OC5A)-Pad38)") (class "Default")
      (node (ref "U1") (pin "38") (pinfunction "PL3_(OC5A)_38") (pintype "passive"))
    )
    (net (code "114") (name "unconnected-(U1-PL4_(OC5B)-Pad39)") (class "Default")
      (node (ref "U1") (pin "39") (pinfunction "PL4_(OC5B)_39") (pintype "passive"))
    )
    (net (code "115") (name "unconnected-(U1-PL5_(OC5C)-Pad40)") (class "Default")
      (node (ref "U1") (pin "40") (pinfunction "PL5_(OC5C)_40") (pintype "passive"))
    )
    (net (code "116") (name "unconnected-(U1-PL6-Pad41)") (class "Default")
      (node (ref "U1") (pin "41") (pinfunction "PL6_41") (pintype "passive"))
    )
    (net (code "117") (name "unconnected-(U2-AVCC-Pad32)") (class "Default")
      (node (ref "U2") (pin "32") (pinfunction "AVCC_32") (pintype "passive"))
    )
    (net (code "118") (name "unconnected-(U2-EP-Pad33)") (class "Default")
      (node (ref "U2") (pin "33") (pinfunction "EP_33") (pintype "passive"))
    )
    (net (code "119") (name "unconnected-(U2-PB0_(SS#{slash}PCINT0)-Pad14)") (class "Default")
      (node (ref "U2") (pin "14") (pinfunction "PB0_(SS#/PCINT0)_14") (pintype "passive"))
    )
    (net (code "120") (name "unconnected-(U2-PB4_(T1{slash}PCINT4)-Pad18)") (class "Default")
      (node (ref "U2") (pin "18") (pinfunction "PB4_(T1/PCINT4)_18") (pintype "passive"))
    )
    (net (code "121") (name "unconnected-(U2-PB5_(PCINT5)-Pad19)") (class "Default")
      (node (ref "U2") (pin "19") (pinfunction "PB5_(PCINT5)_19") (pintype "passive"))
    )
    (net (code "122") (name "unconnected-(U2-PB6_(PCINT6)-Pad20)") (class "Default")
      (node (ref "U2") (pin "20") (pinfunction "PB6_(PCINT6)_20") (pintype "passive"))
    )
    (net (code "123") (name "unconnected-(U2-PB7_(PCINT7{slash}OC.0A{slash}OC.1C)-Pad21)") (class "Default")
      (node (ref "U2") (pin "21") (pinfunction "PB7_(PCINT7/OC.0A/OC.1C)_21") (pintype "passive"))
    )
    (net (code "124") (name "unconnected-(U2-PC2_(PCINT11{slash}AIN2)-Pad5)") (class "Default")
      (node (ref "U2") (pin "5") (pinfunction "PC2_(PCINT11/AIN2)_5") (pintype "passive"))
    )
    (net (code "125") (name "unconnected-(U2-PC4_(PCINT10)-Pad26)") (class "Default")
      (node (ref "U2") (pin "26") (pinfunction "PC4_(PCINT10)_26") (pintype "passive"))
    )
    (net (code "126") (name "unconnected-(U2-PC5_(PCINT9{slash}OC.1B)-Pad25)") (class "Default")
      (node (ref "U2") (pin "25") (pinfunction "PC5_(PCINT9/OC.1B)_25") (pintype "passive"))
    )
    (net (code "127") (name "unconnected-(U2-PC6_(OC.1A{slash}PCINT8)-Pad23)") (class "Default")
      (node (ref "U2") (pin "23") (pinfunction "PC6_(OC.1A/PCINT8)_23") (pintype "passive"))
    )
    (net (code "128") (name "unconnected-(U2-PC7_(INT4{slash}ICP1{slash}CLKO)-Pad22)") (class "Default")
      (node (ref "U2") (pin "22") (pinfunction "PC7_(INT4/ICP1/CLKO)_22") (pintype "passive"))
    )
    (net (code "129") (name "unconnected-(U2-PD0_(OC.0B{slash}INT0)-Pad6)") (class "Default")
      (node (ref "U2") (pin "6") (pinfunction "PD0_(OC.0B/INT0)_6") (pintype "passive"))
    )
    (net (code "130") (name "unconnected-(U2-PD1_(AIN0{slash}INT1)-Pad7)") (class "Default")
      (node (ref "U2") (pin "7") (pinfunction "PD1_(AIN0/INT1)_7") (pintype "passive"))
    )
    (net (code "131") (name "unconnected-(U2-PD6_(RTS#{slash}AIN5{slash}INT6)-Pad12)") (class "Default")
      (node (ref "U2") (pin "12") (pinfunction "PD6_(RTS#/AIN5/INT6)_12") (pintype "passive"))
    )
    (net (code "132") (name "unconnected-(U4-PadID)") (class "Default")
      (node (ref "U4") (pin "ID") (pinfunction "ID_ID") (pintype "passive+no_connect"))
    )
    (net (code "133") (name "unconnected-(U5-1V2O-Pad22)") (class "Default")
      (node (ref "U5") (pin "22") (pinfunction "1V2O_22") (pintype "passive"))
    )
    (net (code "134") (name "unconnected-(U5-ACTLED-Pad27)") (class "Default")
      (node (ref "U5") (pin "27") (pinfunction "ACTLED_27") (pintype "passive"))
    )
    (net (code "135") (name "unconnected-(U5-AGND-Pad3)") (class "Default")
      (node (ref "U5") (pin "3") (pinfunction "AGND_3") (pintype "passive"))
    )
    (net (code "136") (name "unconnected-(U5-AGND-Pad9)") (class "Default")
      (node (ref "U5") (pin "9") (pinfunction "AGND_9") (pintype "passive"))
    )
    (net (code "137") (name "unconnected-(U5-AGND-Pad14)") (class "Default")
      (node (ref "U5") (pin "14") (pinfunction "AGND_14") (pintype "passive"))
    )
    (net (code "138") (name "unconnected-(U5-AGND-Pad16)") (class "Default")
      (node (ref "U5") (pin "16") (pinfunction "AGND_16") (pintype "passive"))
    )
    (net (code "139") (name "unconnected-(U5-AGND-Pad19)") (class "Default")
      (node (ref "U5") (pin "19") (pinfunction "AGND_19") (pintype "passive"))
    )
    (net (code "140") (name "unconnected-(U5-AGND-Pad48)") (class "Default")
      (node (ref "U5") (pin "48") (pinfunction "AGND_48") (pintype "passive"))
    )
    (net (code "141") (name "unconnected-(U5-DNC-Pad7)") (class "Default")
      (node (ref "U5") (pin "7") (pinfunction "DNC_7") (pintype "passive"))
    )
    (net (code "142") (name "unconnected-(U5-DUPLED-Pad26)") (class "Default")
      (node (ref "U5") (pin "26") (pinfunction "DUPLED_26") (pintype "passive"))
    )
    (net (code "143") (name "unconnected-(U5-EXRES1-Pad10)") (class "Default")
      (node (ref "U5") (pin "10") (pinfunction "EXRES1_10") (pintype "passive"))
    )
    (net (code "144") (name "unconnected-(U5-GND-Pad29)") (class "Default")
      (node (ref "U5") (pin "29") (pinfunction "GND_29") (pintype "passive"))
    )
    (net (code "145") (name "unconnected-(U5-INTn-Pad36)") (class "Default")
      (node (ref "U5") (pin "36") (pinfunction "INTn_36") (pintype "passive"))
    )
    (net (code "146") (name "unconnected-(U5-LINKLED-Pad25)") (class "Default")
      (node (ref "U5") (pin "25") (pinfunction "LINKLED_25") (pintype "passive"))
    )
    (net (code "147") (name "unconnected-(U5-MISO-Pad34)") (class "Default")
      (node (ref "U5") (pin "34") (pinfunction "MISO_34") (pintype "passive"))
    )
    (net (code "148") (name "unconnected-(U5-MOSI-Pad35)") (class "Default")
      (node (ref "U5") (pin "35") (pinfunction "MOSI_35") (pintype "passive"))
    )
    (net (code "149") (name "unconnected-(U5-NC-Pad12)") (class "Default")
      (node (ref "U5") (pin "12") (pinfunction "NC_12") (pintype "passive"))
    )
    (net (code "150") (name "unconnected-(U5-NC-Pad13)") (class "Default")
      (node (ref "U5") (pin "13") (pinfunction "NC_13") (pintype "passive"))
    )
    (net (code "151") (name "unconnected-(U5-NC-Pad46)") (class "Default")
      (node (ref "U5") (pin "46") (pinfunction "NC_46") (pintype "passive"))
    )
    (net (code "152") (name "unconnected-(U5-NC-Pad47)") (class "Default")
      (node (ref "U5") (pin "47") (pinfunction "NC_47") (pintype "passive"))
    )
    (net (code "153") (name "unconnected-(U5-PMODE0-Pad45)") (class "Default")
      (node (ref "U5") (pin "45") (pinfunction "PMODE0_45") (pintype "passive"))
    )
    (net (code "154") (name "unconnected-(U5-PMODE1-Pad44)") (class "Default")
      (node (ref "U5") (pin "44") (pinfunction "PMODE1_44") (pintype "passive"))
    )
    (net (code "155") (name "unconnected-(U5-PMODE2-Pad43)") (class "Default")
      (node (ref "U5") (pin "43") (pinfunction "PMODE2_43") (pintype "passive"))
    )
    (net (code "156") (name "unconnected-(U5-RSTn-Pad37)") (class "Default")
      (node (ref "U5") (pin "37") (pinfunction "RSTn_37") (pintype "passive"))
    )
    (net (code "157") (name "unconnected-(U5-RSVD-Pad23)") (class "Default")
      (node (ref "U5") (pin "23") (pinfunction "RSVD_23") (pintype "passive"))
    )
    (net (code "158") (name "unconnected-(U5-RSVD-Pad38)") (class "Default")
      (node (ref "U5") (pin "38") (pinfunction "RSVD_38") (pintype "passive"))
    )
    (net (code "159") (name "unconnected-(U5-RSVD-Pad39)") (class "Default")
      (node (ref "U5") (pin "39") (pinfunction "RSVD_39") (pintype "passive"))
    )
    (net (code "160") (name "unconnected-(U5-RSVD-Pad40)") (class "Default")
      (node (ref "U5") (pin "40") (pinfunction "RSVD_40") (pintype "passive"))
    )
    (net (code "161") (name "unconnected-(U5-RSVD-Pad41)") (class "Default")
      (node (ref "U5") (pin "41") (pinfunction "RSVD_41") (pintype "passive"))
    )
    (net (code "162") (name "unconnected-(U5-RSVD-Pad42)") (class "Default")
      (node (ref "U5") (pin "42") (pinfunction "RSVD_42") (pintype "passive"))
    )
    (net (code "163") (name "unconnected-(U5-RXN-Pad5)") (class "Default")
      (node (ref "U5") (pin "5") (pinfunction "RXN_5") (pintype "passive"))
    )
    (net (code "164") (name "unconnected-(U5-RXP-Pad6)") (class "Default")
      (node (ref "U5") (pin "6") (pinfunction "RXP_6") (pintype "passive"))
    )
    (net (code "165") (name "unconnected-(U5-SCLK-Pad33)") (class "Default")
      (node (ref "U5") (pin "33") (pinfunction "SCLK_33") (pintype "passive"))
    )
    (net (code "166") (name "unconnected-(U5-SCSn-Pad32)") (class "Default")
      (node (ref "U5") (pin "32") (pinfunction "SCSn_32") (pintype "passive"))
    )
    (net (code "167") (name "unconnected-(U5-SPDLED-Pad24)") (class "Default")
      (node (ref "U5") (pin "24") (pinfunction "SPDLED_24") (pintype "passive"))
    )
    (net (code "168") (name "unconnected-(U5-TOCAP-Pad20)") (class "Default")
      (node (ref "U5") (pin "20") (pinfunction "TOCAP_20") (pintype "passive"))
    )
    (net (code "169") (name "unconnected-(U5-TXN-Pad1)") (class "Default")
      (node (ref "U5") (pin "1") (pinfunction "TXN_1") (pintype "passive"))
    )
    (net (code "170") (name "unconnected-(U5-TXP-Pad2)") (class "Default")
      (node (ref "U5") (pin "2") (pinfunction "TXP_2") (pintype "passive"))
    )
    (net (code "171") (name "unconnected-(U5-VBG-Pad18)") (class "Default")
      (node (ref "U5") (pin "18") (pinfunction "VBG_18") (pintype "passive"))
    )
    (net (code "172") (name "unconnected-(U5-VDD-Pad28)") (class "Default")
      (node (ref "U5") (pin "28") (pinfunction "VDD_28") (pintype "passive"))
    )
  )
)
